# ModuleProcessing.net
KiCad netlist of a schematic drawn in EAGLE
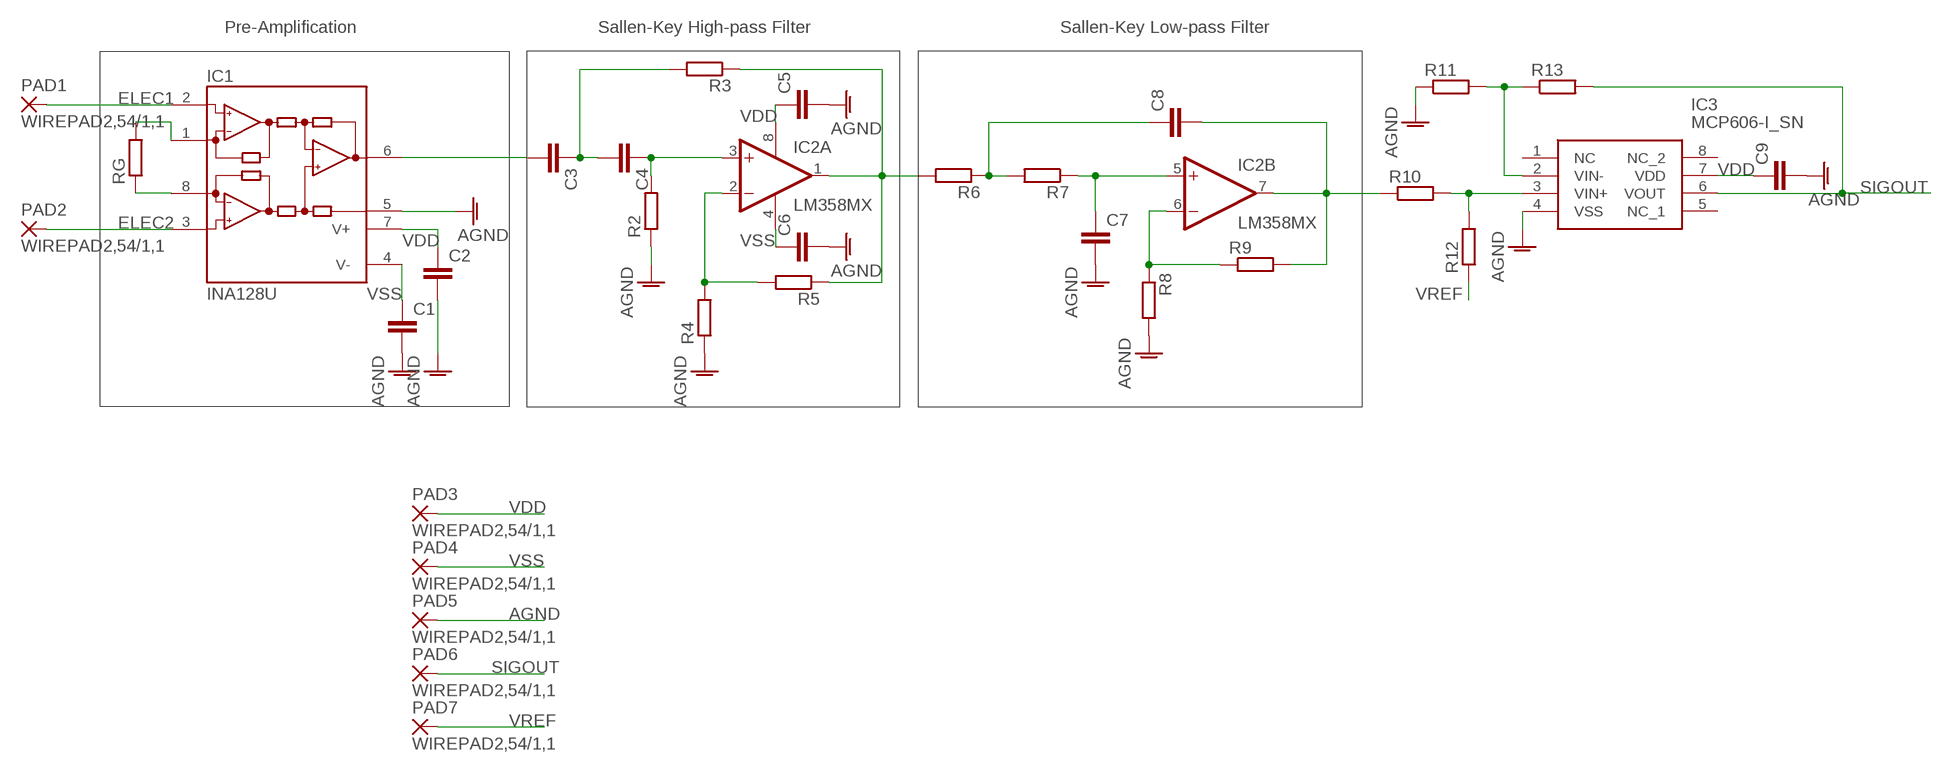
[diagram p0: schematic, sheet 1]

(export (version "E")
  (design (tool "Eeschema 10.0.6"))
  (components
    (comp (ref "C1")
      (value "C-EUC0603")
      (footprint "eagle-import:C0603")
      (libsource (lib "eagle-import") (part "C-EUC0603"))
    )
    (comp (ref "C2")
      (value "C-EUC0603")
      (footprint "eagle-import:C0603")
      (libsource (lib "eagle-import") (part "C-EUC0603"))
    )
    (comp (ref "C3")
      (value "C-EUC0603")
      (footprint "eagle-import:C0603")
      (libsource (lib "eagle-import") (part "C-EUC0603"))
    )
    (comp (ref "C4")
      (value "C-EUC0603")
      (footprint "eagle-import:C0603")
      (libsource (lib "eagle-import") (part "C-EUC0603"))
    )
    (comp (ref "C5")
      (value "C-EUC0603")
      (footprint "eagle-import:C0603")
      (libsource (lib "eagle-import") (part "C-EUC0603"))
    )
    (comp (ref "C6")
      (value "C-EUC0603")
      (footprint "eagle-import:C0603")
      (libsource (lib "eagle-import") (part "C-EUC0603"))
    )
    (comp (ref "C7")
      (value "C-EUC0603")
      (footprint "eagle-import:C0603")
      (libsource (lib "eagle-import") (part "C-EUC0603"))
    )
    (comp (ref "C8")
      (value "C-EUC0603")
      (footprint "eagle-import:C0603")
      (libsource (lib "eagle-import") (part "C-EUC0603"))
    )
    (comp (ref "C9")
      (value "C-EUC0603")
      (footprint "eagle-import:C0603")
      (libsource (lib "eagle-import") (part "C-EUC0603"))
    )
    (comp (ref "IC1")
      (value "INA128U")
      (footprint "eagle-import:SO08")
      (fields (field (name "MF") "TEXAS INSTRUMENTS"))
      (libsource (lib "eagle-import") (part "INA128U"))
    )
    (comp (ref "IC2")
      (value "LM358MX")
      (footprint "eagle-import:SO08")
      (fields (field (name "SPICEPREFIX") "J"))
      (libsource (lib "eagle-import") (part "LM358MX"))
    )
    (comp (ref "IC3")
      (value "MCP606-I_SN")
      (footprint "eagle-import:SOIC127P600X175-8N")
      (fields (field (name "ARROW_PART_NUMBER") "MCP606-I/SN") (field (name "RS_PART_NUMBER") "0403002P"))
      (libsource (lib "eagle-import") (part "MCP606-I_SN"))
    )
    (comp (ref "PAD1")
      (value "WIREPAD2,54/1,1")
      (footprint "eagle-import:2,54_1,1")
      (libsource (lib "eagle-import") (part "WIREPAD2,54/1,1"))
    )
    (comp (ref "PAD2")
      (value "WIREPAD2,54/1,1")
      (footprint "eagle-import:2,54_1,1")
      (libsource (lib "eagle-import") (part "WIREPAD2,54/1,1"))
    )
    (comp (ref "PAD3")
      (value "WIREPAD2,54/1,1")
      (footprint "eagle-import:2,54_1,1")
      (libsource (lib "eagle-import") (part "WIREPAD2,54/1,1"))
    )
    (comp (ref "PAD4")
      (value "WIREPAD2,54/1,1")
      (footprint "eagle-import:2,54_1,1")
      (libsource (lib "eagle-import") (part "WIREPAD2,54/1,1"))
    )
    (comp (ref "PAD5")
      (value "WIREPAD2,54/1,1")
      (footprint "eagle-import:2,54_1,1")
      (libsource (lib "eagle-import") (part "WIREPAD2,54/1,1"))
    )
    (comp (ref "PAD6")
      (value "WIREPAD2,54/1,1")
      (footprint "eagle-import:2,54_1,1")
      (libsource (lib "eagle-import") (part "WIREPAD2,54/1,1"))
    )
    (comp (ref "PAD7")
      (value "WIREPAD2,54/1,1")
      (footprint "eagle-import:2,54_1,1")
      (libsource (lib "eagle-import") (part "WIREPAD2,54/1,1"))
    )
    (comp (ref "R2")
      (value "R-EU_0207/10")
      (footprint "eagle-import:0207_10")
      (libsource (lib "eagle-import") (part "R-EU_0207/10"))
    )
    (comp (ref "R3")
      (value "R-EU_0207/10")
      (footprint "eagle-import:0207_10")
      (libsource (lib "eagle-import") (part "R-EU_0207/10"))
    )
    (comp (ref "R4")
      (value "R-EU_0207/10")
      (footprint "eagle-import:0207_10")
      (libsource (lib "eagle-import") (part "R-EU_0207/10"))
    )
    (comp (ref "R5")
      (value "R-EU_0207/10")
      (footprint "eagle-import:0207_10")
      (libsource (lib "eagle-import") (part "R-EU_0207/10"))
    )
    (comp (ref "R6")
      (value "R-EU_0207/10")
      (footprint "eagle-import:0207_10")
      (libsource (lib "eagle-import") (part "R-EU_0207/10"))
    )
    (comp (ref "R7")
      (value "R-EU_0207/10")
      (footprint "eagle-import:0207_10")
      (libsource (lib "eagle-import") (part "R-EU_0207/10"))
    )
    (comp (ref "R8")
      (value "R-EU_0207/10")
      (footprint "eagle-import:0207_10")
      (libsource (lib "eagle-import") (part "R-EU_0207/10"))
    )
    (comp (ref "R9")
      (value "R-EU_0207/10")
      (footprint "eagle-import:0207_10")
      (libsource (lib "eagle-import") (part "R-EU_0207/10"))
    )
    (comp (ref "R10")
      (value "R-EU_0207/10")
      (footprint "eagle-import:0207_10")
      (libsource (lib "eagle-import") (part "R-EU_0207/10"))
    )
    (comp (ref "R11")
      (value "R-EU_0207/10")
      (footprint "eagle-import:0207_10")
      (libsource (lib "eagle-import") (part "R-EU_0207/10"))
    )
    (comp (ref "R12")
      (value "R-EU_0207/10")
      (footprint "eagle-import:0207_10")
      (libsource (lib "eagle-import") (part "R-EU_0207/10"))
    )
    (comp (ref "R13")
      (value "R-EU_0207/10")
      (footprint "eagle-import:0207_10")
      (libsource (lib "eagle-import") (part "R-EU_0207/10"))
    )
    (comp (ref "RG")
      (value "R-EU_0207/10")
      (footprint "eagle-import:0207_10")
      (libsource (lib "eagle-import") (part "R-EU_0207/10"))
    )
  )
  (nets
    (net (code "1") (name "/ELEC1") (class "Default")
      (node (ref "IC1") (pin "2") (pinfunction "-IN_2") (pintype "input"))
      (node (ref "PAD1") (pin "1") (pinfunction "P_1") (pintype "passive"))
    )
    (net (code "2") (name "/ELEC2") (class "Default")
      (node (ref "IC1") (pin "3") (pinfunction "+IN_3") (pintype "input"))
      (node (ref "PAD2") (pin "1") (pinfunction "P_1") (pintype "passive"))
    )
    (net (code "3") (name "/SIGOUT") (class "Default")
      (node (ref "IC3") (pin "6") (pinfunction "VOUT_6") (pintype "output"))
      (node (ref "PAD6") (pin "1") (pinfunction "P_1") (pintype "passive"))
      (node (ref "R13") (pin "2") (pinfunction "2_2") (pintype "passive"))
    )
    (net (code "4") (name "/VDD") (class "Default")
      (node (ref "C2") (pin "1") (pinfunction "1_1") (pintype "passive"))
      (node (ref "C5") (pin "1") (pinfunction "1_1") (pintype "passive"))
      (node (ref "C9") (pin "1") (pinfunction "1_1") (pintype "passive"))
      (node (ref "IC1") (pin "7") (pinfunction "V+_7") (pintype "power_in"))
      (node (ref "IC2") (pin "8") (pinfunction "V+_8") (pintype "power_in"))
      (node (ref "IC3") (pin "7") (pinfunction "VDD_7") (pintype "power_in"))
      (node (ref "PAD3") (pin "1") (pinfunction "P_1") (pintype "passive"))
    )
    (net (code "5") (name "/VREF") (class "Default")
      (node (ref "PAD7") (pin "1") (pinfunction "P_1") (pintype "passive"))
      (node (ref "R12") (pin "1") (pinfunction "1_1") (pintype "passive"))
    )
    (net (code "6") (name "/VSS") (class "Default")
      (node (ref "C1") (pin "1") (pinfunction "1_1") (pintype "passive"))
      (node (ref "C6") (pin "1") (pinfunction "1_1") (pintype "passive"))
      (node (ref "IC1") (pin "4") (pinfunction "V-_4") (pintype "power_in"))
      (node (ref "IC2") (pin "4") (pinfunction "V-_4") (pintype "power_in"))
      (node (ref "PAD4") (pin "1") (pinfunction "P_1") (pintype "passive"))
    )
    (net (code "7") (name "AGND") (class "Default")
      (node (ref "C1") (pin "2") (pinfunction "2_2") (pintype "passive"))
      (node (ref "C2") (pin "2") (pinfunction "2_2") (pintype "passive"))
      (node (ref "C5") (pin "2") (pinfunction "2_2") (pintype "passive"))
      (node (ref "C6") (pin "2") (pinfunction "2_2") (pintype "passive"))
      (node (ref "C7") (pin "2") (pinfunction "2_2") (pintype "passive"))
      (node (ref "C9") (pin "2") (pinfunction "2_2") (pintype "passive"))
      (node (ref "IC1") (pin "5") (pinfunction "REF_5") (pintype "passive"))
      (node (ref "IC3") (pin "4") (pinfunction "VSS_4") (pintype "power_in"))
      (node (ref "PAD5") (pin "1") (pinfunction "P_1") (pintype "passive"))
      (node (ref "R11") (pin "1") (pinfunction "1_1") (pintype "passive"))
      (node (ref "R2") (pin "1") (pinfunction "1_1") (pintype "passive"))
      (node (ref "R4") (pin "1") (pinfunction "1_1") (pintype "passive"))
      (node (ref "R8") (pin "2") (pinfunction "2_2") (pintype "passive"))
    )
    (net (code "8") (name "Net-(C3-Pad1)") (class "Default")
      (node (ref "C3") (pin "1") (pinfunction "1_1") (pintype "passive"))
      (node (ref "C4") (pin "2") (pinfunction "2_2") (pintype "passive"))
      (node (ref "R3") (pin "2") (pinfunction "2_2") (pintype "passive"))
    )
    (net (code "9") (name "Net-(C8-Pad1)") (class "Default")
      (node (ref "C8") (pin "1") (pinfunction "1_1") (pintype "passive"))
      (node (ref "R6") (pin "1") (pinfunction "1_1") (pintype "passive"))
      (node (ref "R7") (pin "2") (pinfunction "2_2") (pintype "passive"))
    )
    (net (code "10") (name "Net-(IC1-OUT)") (class "Default")
      (node (ref "C3") (pin "2") (pinfunction "2_2") (pintype "passive"))
      (node (ref "IC1") (pin "6") (pinfunction "OUT_6") (pintype "output"))
    )
    (net (code "11") (name "Net-(IC1-RG-Pad1)") (class "Default")
      (node (ref "IC1") (pin "1") (pinfunction "RG_1") (pintype "passive"))
      (node (ref "RG") (pin "2") (pinfunction "2_2") (pintype "passive"))
    )
    (net (code "12") (name "Net-(IC1-RG-Pad8)") (class "Default")
      (node (ref "IC1") (pin "8") (pinfunction "RG_8") (pintype "passive"))
      (node (ref "RG") (pin "1") (pinfunction "1_1") (pintype "passive"))
    )
    (net (code "13") (name "Net-(IC2A-+IN)") (class "Default")
      (node (ref "C4") (pin "1") (pinfunction "1_1") (pintype "passive"))
      (node (ref "IC2") (pin "3") (pinfunction "+IN_3") (pintype "input"))
      (node (ref "R2") (pin "2") (pinfunction "2_2") (pintype "passive"))
    )
    (net (code "14") (name "Net-(IC2A--IN)") (class "Default")
      (node (ref "IC2") (pin "2") (pinfunction "-IN_2") (pintype "input"))
      (node (ref "R4") (pin "2") (pinfunction "2_2") (pintype "passive"))
      (node (ref "R5") (pin "2") (pinfunction "2_2") (pintype "passive"))
    )
    (net (code "15") (name "Net-(IC2A-OUT)") (class "Default")
      (node (ref "IC2") (pin "1") (pinfunction "OUT_1") (pintype "output"))
      (node (ref "R3") (pin "1") (pinfunction "1_1") (pintype "passive"))
      (node (ref "R5") (pin "1") (pinfunction "1_1") (pintype "passive"))
      (node (ref "R6") (pin "2") (pinfunction "2_2") (pintype "passive"))
    )
    (net (code "16") (name "Net-(IC2B-+IN)") (class "Default")
      (node (ref "C7") (pin "1") (pinfunction "1_1") (pintype "passive"))
      (node (ref "IC2") (pin "5") (pinfunction "+IN_5") (pintype "input"))
      (node (ref "R7") (pin "1") (pinfunction "1_1") (pintype "passive"))
    )
    (net (code "17") (name "Net-(IC2B--IN)") (class "Default")
      (node (ref "IC2") (pin "6") (pinfunction "-IN_6") (pintype "input"))
      (node (ref "R8") (pin "1") (pinfunction "1_1") (pintype "passive"))
      (node (ref "R9") (pin "1") (pinfunction "1_1") (pintype "passive"))
    )
    (net (code "18") (name "Net-(IC2B-OUT)") (class "Default")
      (node (ref "C8") (pin "2") (pinfunction "2_2") (pintype "passive"))
      (node (ref "IC2") (pin "7") (pinfunction "OUT_7") (pintype "output"))
      (node (ref "R10") (pin "1") (pinfunction "1_1") (pintype "passive"))
      (node (ref "R9") (pin "2") (pinfunction "2_2") (pintype "passive"))
    )
    (net (code "19") (name "Net-(IC3-VIN+)") (class "Default")
      (node (ref "IC3") (pin "3") (pinfunction "VIN+_3") (pintype "input"))
      (node (ref "R10") (pin "2") (pinfunction "2_2") (pintype "passive"))
      (node (ref "R12") (pin "2") (pinfunction "2_2") (pintype "passive"))
    )
    (net (code "20") (name "Net-(IC3-VIN-)") (class "Default")
      (node (ref "IC3") (pin "2") (pinfunction "VIN-_2") (pintype "input"))
      (node (ref "R11") (pin "2") (pinfunction "2_2") (pintype "passive"))
      (node (ref "R13") (pin "1") (pinfunction "1_1") (pintype "passive"))
    )
    (net (code "21") (name "unconnected-(IC3-NC-Pad1)") (class "Default")
      (node (ref "IC3") (pin "1") (pinfunction "NC_1") (pintype "no_connect"))
    )
    (net (code "22") (name "unconnected-(IC3-NC_1-Pad5)") (class "Default")
      (node (ref "IC3") (pin "5") (pinfunction "NC_1_5") (pintype "bidirectional"))
    )
    (net (code "23") (name "unconnected-(IC3-NC_2-Pad8)") (class "Default")
      (node (ref "IC3") (pin "8") (pinfunction "NC_2_8") (pintype "bidirectional"))
    )
  )
)
